# Whitespace_Daughtercard_top_level.net
KiCad netlist of a schematic drawn in Altium Designer
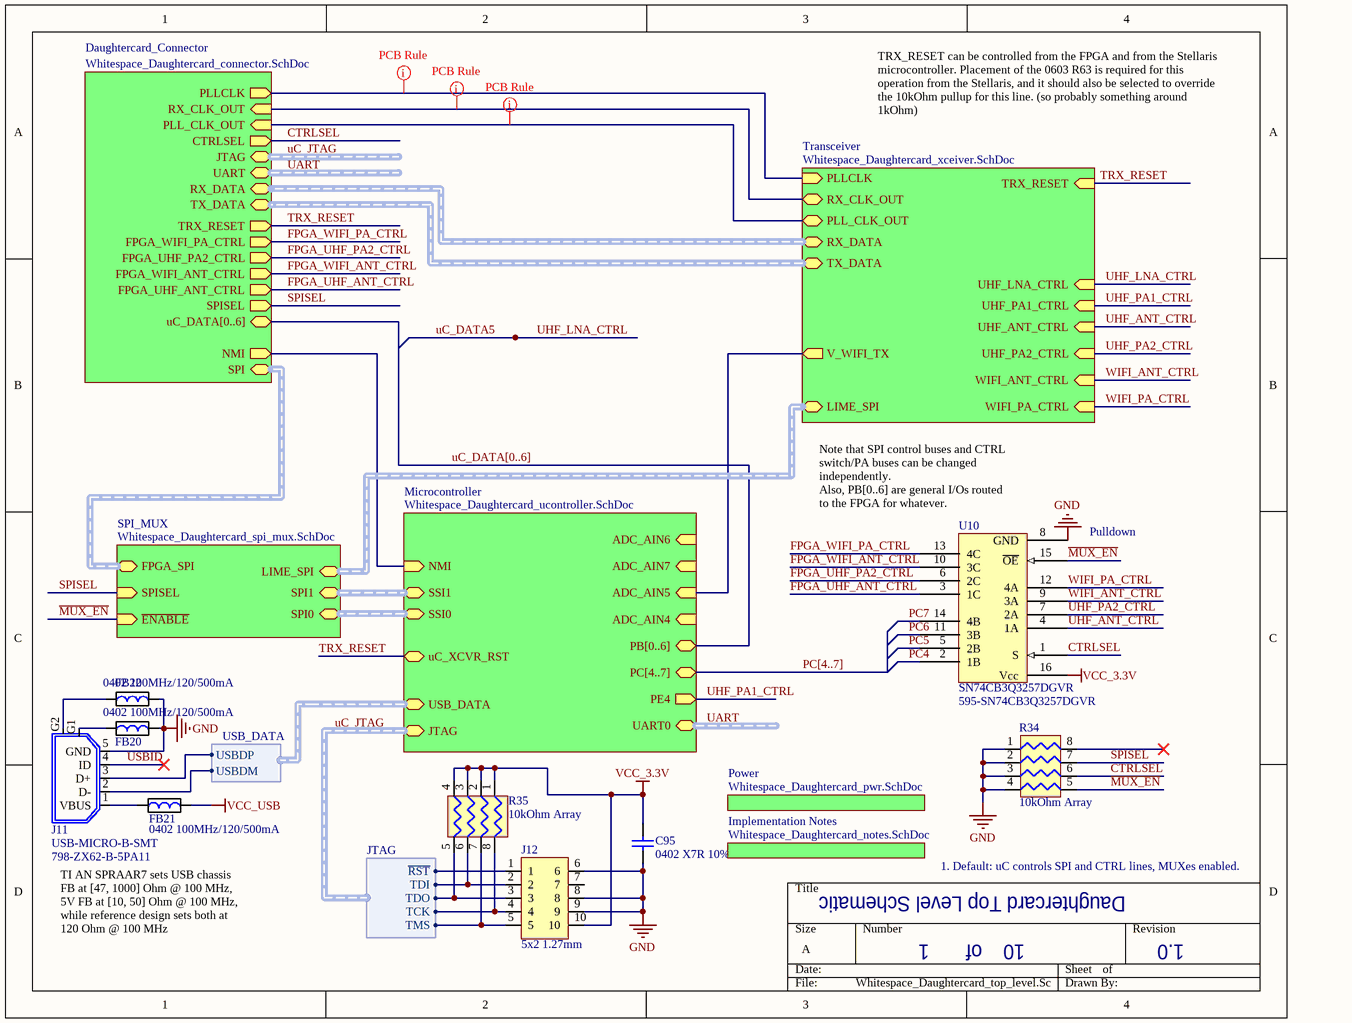
[diagram p0: Whitespace_Daughtercard_top_level.SchDoc]

(export (version "E")
  (design (tool "Eeschema 10.0.6"))
  (components
    (comp (ref "C95")
      (value "0402 X7R 10%")
      (footprint "0402_SMT_V3")
      (description "Capacitor")
      (fields (field (name "PUBLISHER") "Altium Limited"))
      (libsource (lib "Miscellaneous Devices") (part "Cap"))
    )
    (comp (ref "FB20")
      (value "0402 100MHz/120/500mA")
      (footprint "0402_SMT_v3")
      (description "Ferrite Bead, Various Values")
      (libsource (lib "RNG_Parts") (part "FERRITE_BEAD"))
    )
    (comp (ref "FB21")
      (value "0402 100MHz/120/500mA")
      (footprint "0402_SMT_v3")
      (description "Ferrite Bead, Various Values")
      (libsource (lib "RNG_Parts") (part "FERRITE_BEAD"))
    )
    (comp (ref "FB22")
      (value "0402 100MHz/120/500mA")
      (footprint "0402_SMT_v3")
      (description "Ferrite Bead, Various Values")
      (libsource (lib "RNG_Parts") (part "FERRITE_BEAD"))
    )
    (comp (ref "J11")
      (value "USB-MICRO-B-SMT")
      (footprint "USB_MICROB_SMT_R3")
      (description "Molex Micro-USB Type B Connector")
      (fields (field (name "SUPPLIER PART NUMBER 1") "798-ZX62-B-5PA11"))
      (libsource (lib "RNG_Parts") (part "USB-MICRO-B-SMT"))
    )
    (comp (ref "J12")
      (value "5x2 1.27mm")
      (footprint "1.27mm_2x5_SMT_HDR")
      (description "5X2 1.27 SMT Header Pins")
      (libsource (lib "RNG_Parts") (part "Header_5x2_FinePitch_1.27mm"))
    )
    (comp (ref "R34")
      (value "10kOhm Array")
      (footprint "741X083_ChipArray_0402x4_v2")
      (description "10kOhm Ohm 4x0402 Resistor Array")
      (libsource (lib "") (part "741X083103JP_1"))
    )
    (comp (ref "R35")
      (value "10kOhm Array")
      (footprint "741X083_ChipArray_0402x4_v2")
      (description "10kOhm Ohm 4x0402 Resistor Array")
      (libsource (lib "RNG_Parts") (part "741X083103JP"))
    )
    (comp (ref "U10")
      (value "SN74CB3Q3257DGVR")
      (footprint "TVSOP16_v5")
      (description "4-bit MUX/DEMUX 1-of-2  0-5V SIG 3.3V CTRL TVSOP-16")
      (fields (field (name "SUPPLIER PART NUMBER 1") "595-SN74CB3Q3257DGVR"))
      (libsource (lib "RNG_Parts") (part "SN74CB3Q3257DGVR"))
    )
  )
  (nets
    (net (code "14") (name "/CTRLSEL") (class "Default")
      (node (ref "R34") (pin "6") (pinfunction "6_6") (pintype "passive"))
      (node (ref "U10") (pin "1") (pinfunction "S_1") (pintype "input"))
    )
    (net (code "16") (name "/FPGA_UHF_ANT_CTRL") (class "Default")
      (node (ref "U10") (pin "3") (pinfunction "1C_3") (pintype "passive"))
    )
    (net (code "17") (name "/FPGA_UHF_PA2_CTRL") (class "Default")
      (node (ref "U10") (pin "6") (pinfunction "2C_6") (pintype "passive"))
    )
    (net (code "18") (name "/FPGA_WIFI_ANT_CTRL") (class "Default")
      (node (ref "U10") (pin "10") (pinfunction "3C_10") (pintype "passive"))
    )
    (net (code "19") (name "/FPGA_WIFI_PA_CTRL") (class "Default")
      (node (ref "U10") (pin "13") (pinfunction "4C_13") (pintype "passive"))
    )
    (net (code "21") (name "/MUX_EN") (class "Default")
      (node (ref "R34") (pin "5") (pinfunction "5_5") (pintype "passive"))
      (node (ref "U10") (pin "15") (pinfunction "OE_15") (pintype "input"))
    )
    (net (code "23") (name "/PC4") (class "Default")
      (node (ref "U10") (pin "2") (pinfunction "1B_2") (pintype "passive"))
    )
    (net (code "24") (name "/PC5") (class "Default")
      (node (ref "U10") (pin "5") (pinfunction "2B_5") (pintype "passive"))
    )
    (net (code "25") (name "/PC6") (class "Default")
      (node (ref "U10") (pin "11") (pinfunction "3B_11") (pintype "passive"))
    )
    (net (code "26") (name "/PC7") (class "Default")
      (node (ref "U10") (pin "14") (pinfunction "4B_14") (pintype "passive"))
    )
    (net (code "34") (name "/SPISEL") (class "Default")
      (node (ref "R34") (pin "7") (pinfunction "7_7") (pintype "passive"))
    )
    (net (code "35") (name "/TCK") (class "Default")
      (node (ref "J12") (pin "4") (pinfunction "4_4") (pintype "passive"))
      (node (ref "R35") (pin "8") (pinfunction "8_8") (pintype "passive"))
    )
    (net (code "36") (name "/TDI") (class "Default")
      (node (ref "J12") (pin "2") (pinfunction "2_2") (pintype "passive"))
      (node (ref "R35") (pin "6") (pinfunction "6_6") (pintype "passive"))
    )
    (net (code "37") (name "/TDO") (class "Default")
      (node (ref "J12") (pin "3") (pinfunction "3_3") (pintype "passive"))
      (node (ref "R35") (pin "5") (pinfunction "5_5") (pintype "passive"))
    )
    (net (code "38") (name "/TMS") (class "Default")
      (node (ref "J12") (pin "5") (pinfunction "5_5") (pintype "passive"))
      (node (ref "R35") (pin "7") (pinfunction "7_7") (pintype "passive"))
    )
    (net (code "41") (name "/UHF_ANT_CTRL") (class "Default")
      (node (ref "U10") (pin "4") (pinfunction "1A_4") (pintype "passive"))
    )
    (net (code "43") (name "/UHF_PA2_CTRL") (class "Default")
      (node (ref "U10") (pin "7") (pinfunction "2A_7") (pintype "passive"))
    )
    (net (code "44") (name "/USBDM") (class "Default")
      (node (ref "J11") (pin "2") (pinfunction "D-_2") (pintype "passive"))
    )
    (net (code "45") (name "/USBDP") (class "Default")
      (node (ref "J11") (pin "3") (pinfunction "D+_3") (pintype "passive"))
    )
    (net (code "46") (name "/USBID") (class "Default")
      (node (ref "J11") (pin "4") (pinfunction "ID_4") (pintype "passive+no_connect"))
    )
    (net (code "48") (name "/WIFI_ANT_CTRL") (class "Default")
      (node (ref "U10") (pin "9") (pinfunction "3A_9") (pintype "passive"))
    )
    (net (code "49") (name "/WIFI_PA_CTRL") (class "Default")
      (node (ref "U10") (pin "12") (pinfunction "4A_12") (pintype "passive"))
    )
    (net (code "56") (name "/~{RST}") (class "Default")
      (node (ref "J12") (pin "1") (pinfunction "1_1") (pintype "passive"))
    )
    (net (code "57") (name "GND") (class "Default")
      (node (ref "C95") (pin "2") (pinfunction "2_2") (pintype "passive"))
      (node (ref "FB20") (pin "2") (pinfunction "2_2") (pintype "passive"))
      (node (ref "FB22") (pin "2") (pinfunction "2_2") (pintype "passive"))
      (node (ref "J11") (pin "5") (pinfunction "GND_5") (pintype "power_in"))
      (node (ref "J12") (pin "6") (pinfunction "6_6") (pintype "passive"))
      (node (ref "J12") (pin "8") (pinfunction "8_8") (pintype "passive"))
      (node (ref "J12") (pin "9") (pinfunction "9_9") (pintype "passive"))
      (node (ref "R34") (pin "1") (pinfunction "1_1") (pintype "passive"))
      (node (ref "R34") (pin "2") (pinfunction "2_2") (pintype "passive"))
      (node (ref "R34") (pin "3") (pinfunction "3_3") (pintype "passive"))
      (node (ref "R34") (pin "4") (pinfunction "4_4") (pintype "passive"))
      (node (ref "U10") (pin "8") (pinfunction "GND_8") (pintype "power_in"))
    )
    (net (code "58") (name "Net-(J11-Chassis_GND)") (class "Default")
      (node (ref "FB22") (pin "1") (pinfunction "1_1") (pintype "passive"))
      (node (ref "J11") (pin "G2") (pinfunction "Chassis_GND_G2") (pintype "passive"))
    )
    (net (code "59") (name "Net-(J11-Chassis_Ground)") (class "Default")
      (node (ref "FB20") (pin "1") (pinfunction "1_1") (pintype "passive"))
      (node (ref "J11") (pin "G1") (pinfunction "Chassis_Ground_G1") (pintype "passive"))
    )
    (net (code "60") (name "Net-(J11-VBUS)") (class "Default")
      (node (ref "FB21") (pin "1") (pinfunction "1_1") (pintype "passive"))
      (node (ref "J11") (pin "1") (pinfunction "VBUS_1") (pintype "power_in"))
    )
    (net (code "61") (name "VCC_3.3V") (class "Default")
      (node (ref "C95") (pin "1") (pinfunction "1_1") (pintype "passive"))
      (node (ref "J12") (pin "10") (pinfunction "10_10") (pintype "passive"))
      (node (ref "R35") (pin "1") (pinfunction "1_1") (pintype "passive"))
      (node (ref "R35") (pin "2") (pinfunction "2_2") (pintype "passive"))
      (node (ref "R35") (pin "3") (pinfunction "3_3") (pintype "passive"))
      (node (ref "R35") (pin "4") (pinfunction "4_4") (pintype "passive"))
      (node (ref "U10") (pin "16") (pinfunction "Vcc_16") (pintype "power_in"))
    )
    (net (code "62") (name "VCC_USB") (class "Default")
      (node (ref "FB21") (pin "2") (pinfunction "2_2") (pintype "passive"))
    )
    (net (code "63") (name "unconnected-(J12-Pad7)") (class "Default")
      (node (ref "J12") (pin "7") (pinfunction "7_7") (pintype "passive"))
    )
    (net (code "64") (name "unconnected-(R34-Pad8)") (class "Default")
      (node (ref "R34") (pin "8") (pinfunction "8_8") (pintype "passive+no_connect"))
    )
  )
)
